# LED_Emergency_warning_lights.net
KiCad netlist of a schematic drawn in Altium Designer
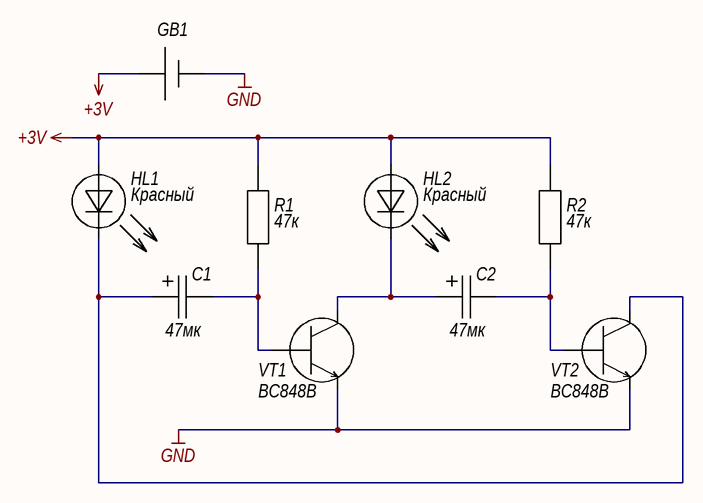
[diagram p0: LED_Emergency_warning_lights.SchDoc]

(export (version "E")
  (design (tool "Eeschema 10.0.6"))
  (components
    (comp (ref "C1")
      (value "47мк")
      (footprint "0607_ELECTR_CAP")
      (fields (field (name "TOLERANCE") "20%") (field (name "VOLTAGE") "35"))
      (libsource (lib "LED_Emergency_warning_lights") (part "Capacitor_pol"))
    )
    (comp (ref "C2")
      (value "47мк")
      (footprint "0607_ELECTR_CAP")
      (fields (field (name "TOLERANCE") "20%") (field (name "VOLTAGE") "35"))
      (libsource (lib "LED_Emergency_warning_lights") (part "Capacitor_pol"))
    )
    (comp (ref "GB1")
      (value "BA2032SM")
      (footprint "FP-653-MFG")
      (libsource (lib "LED_Emergency_warning_lights") (part "Battery"))
    )
    (comp (ref "HL1")
      (value "Красный")
      (footprint "0603_LED_RED")
      (fields (field (name "VALUEMANUFACTURERPARTNUMBER") "FYLS-0603URC"))
      (libsource (lib "LED_Emergency_warning_lights") (part "Led_red"))
    )
    (comp (ref "HL2")
      (value "Красный")
      (footprint "0603_LED_RED")
      (fields (field (name "VALUEMANUFACTURERPARTNUMBER") "FYLS-0603URC"))
      (libsource (lib "LED_Emergency_warning_lights") (part "Led_red"))
    )
    (comp (ref "R1")
      (value "47к")
      (footprint "0603_RES")
      (fields
        (field (name "TOLERANCE") "1%")
        (field (name "POWER") "0,1")
        (field (name "VALUEMANUFACTURERPARTNUMBER") "RC0603FR-0747KL")
      )
      (libsource (lib "LED_Emergency_warning_lights") (part "Resistor"))
    )
    (comp (ref "R2")
      (value "47к")
      (footprint "0603_RES")
      (fields
        (field (name "TOLERANCE") "1%")
        (field (name "POWER") "0,1")
        (field (name "VALUEMANUFACTURERPARTNUMBER") "RC0603FR-0747KL")
      )
      (libsource (lib "LED_Emergency_warning_lights") (part "Resistor"))
    )
    (comp (ref "VT1")
      (value "BC848B")
      (footprint "SOT-23")
      (fields (field (name "VALUEMANUFACTURERPARTNUMBER") "BC848B,215"))
      (libsource (lib "LED_Emergency_warning_lights") (part "NPN_BEC"))
    )
    (comp (ref "VT2")
      (value "BC848B")
      (footprint "SOT-23")
      (fields (field (name "VALUEMANUFACTURERPARTNUMBER") "BC848B,215"))
      (libsource (lib "LED_Emergency_warning_lights") (part "NPN_BEC"))
    )
  )
  (nets
    (net (code "1") (name "+3V") (class "Default")
      (node (ref "GB1") (pin "P") (pinfunction "P_P") (pintype "passive"))
      (node (ref "HL1") (pin "A") (pinfunction "1_A") (pintype "passive"))
      (node (ref "HL2") (pin "A") (pinfunction "1_A") (pintype "passive"))
      (node (ref "R1") (pin "1") (pinfunction "1_1") (pintype "passive"))
      (node (ref "R2") (pin "1") (pinfunction "1_1") (pintype "passive"))
    )
    (net (code "2") (name "GND") (class "Default")
      (node (ref "GB1") (pin "N") (pinfunction "N_N") (pintype "passive"))
      (node (ref "VT1") (pin "2") (pinfunction "e_2") (pintype "passive"))
      (node (ref "VT2") (pin "2") (pinfunction "e_2") (pintype "passive"))
    )
    (net (code "3") (name "Net-(HL1-2)") (class "Default")
      (node (ref "C1") (pin "1") (pinfunction "1_1") (pintype "passive"))
      (node (ref "HL1") (pin "K") (pinfunction "2_K") (pintype "passive"))
      (node (ref "VT2") (pin "3") (pinfunction "c_3") (pintype "passive"))
    )
    (net (code "4") (name "Net-(HL2-2)") (class "Default")
      (node (ref "C2") (pin "1") (pinfunction "1_1") (pintype "passive"))
      (node (ref "HL2") (pin "K") (pinfunction "2_K") (pintype "passive"))
      (node (ref "VT1") (pin "3") (pinfunction "c_3") (pintype "passive"))
    )
    (net (code "5") (name "Net-(VT1-b)") (class "Default")
      (node (ref "C1") (pin "2") (pinfunction "2_2") (pintype "passive"))
      (node (ref "R1") (pin "2") (pinfunction "2_2") (pintype "passive"))
      (node (ref "VT1") (pin "1") (pinfunction "b_1") (pintype "passive"))
    )
    (net (code "6") (name "Net-(VT2-b)") (class "Default")
      (node (ref "C2") (pin "2") (pinfunction "2_2") (pintype "passive"))
      (node (ref "R2") (pin "2") (pinfunction "2_2") (pintype "passive"))
      (node (ref "VT2") (pin "1") (pinfunction "b_1") (pintype "passive"))
    )
  )
)
